# DCI_Connectors.net
KiCad netlist of a schematic drawn in Altium Designer
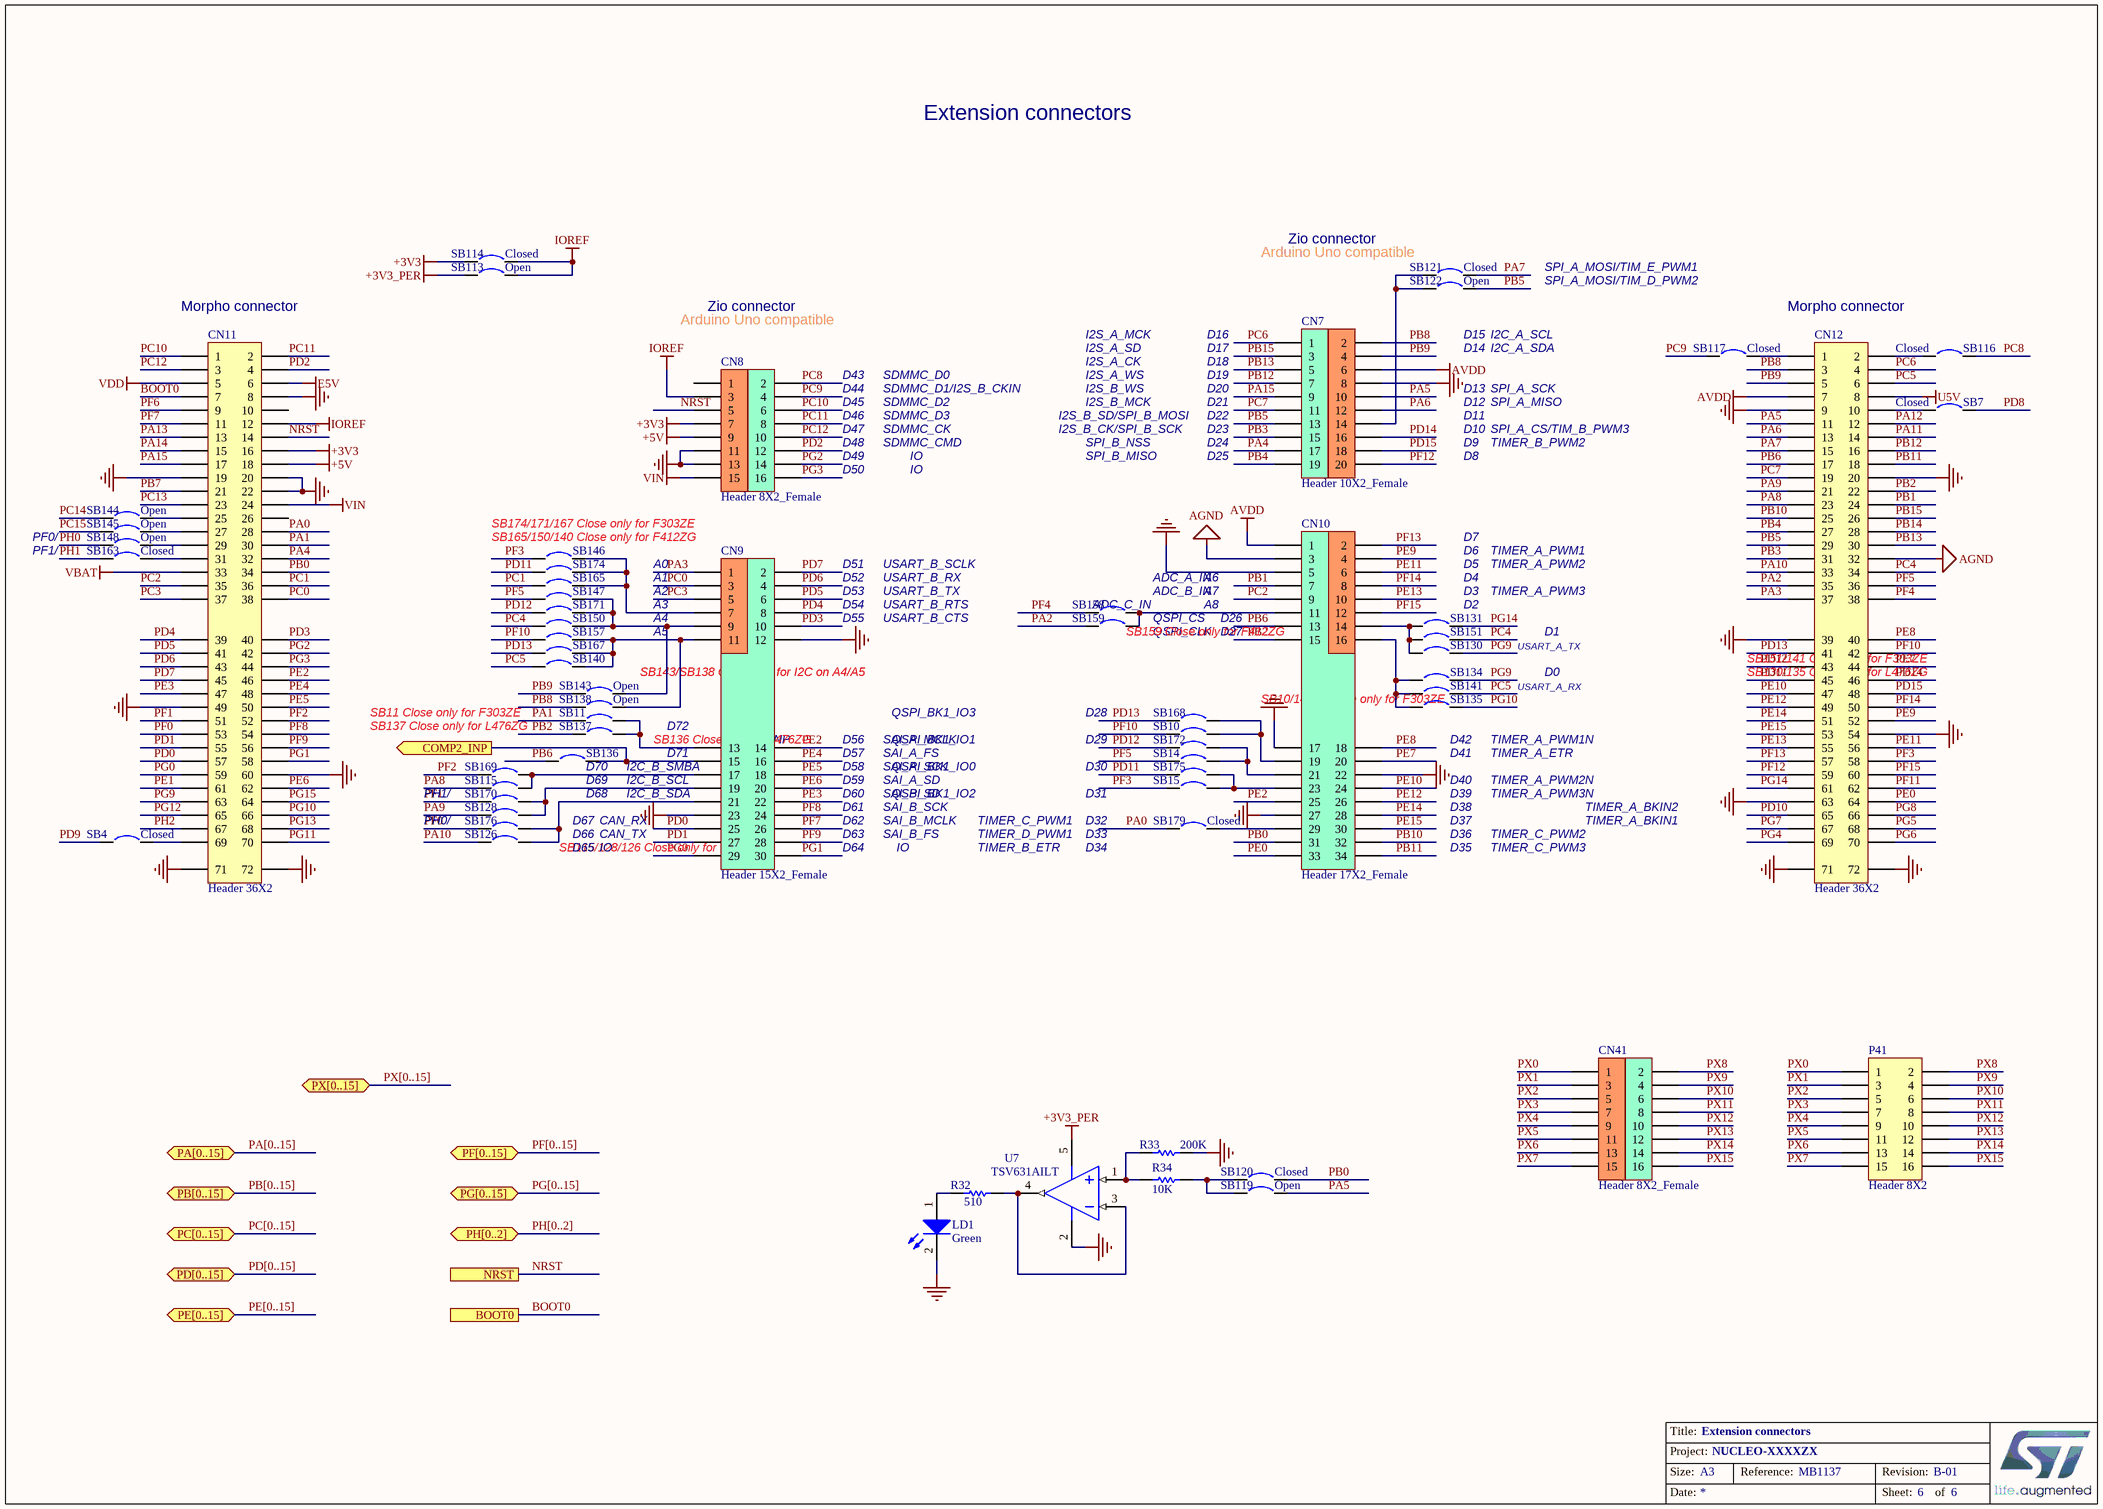
[diagram p0: DCI_Connectors.SchDoc]

(export (version "E")
  (design (tool "Eeschema 10.0.6"))
  (components
    (comp (ref "CN7")
      (value "Header 10X2_Female")
      (footprint "HDR_10x2_2R54_V_F")
      (description "Header, 10-Pin, Dual row,female")
      (fields (field (name "PUBLISHER") "Altium Limited"))
      (libsource (lib "MB1137") (part "Header 10X2_Female"))
    )
    (comp (ref "CN8")
      (value "Header 8X2_Female")
      (footprint "HDR_8x2_2R54_V_F")
      (description "Header, 8-Pin, Dual row,female")
      (fields (field (name "PUBLISHER") "Altium Limited"))
      (libsource (lib "MB1137") (part "Header 8X2_Female"))
    )
    (comp (ref "CN9")
      (value "Header 15X2_Female")
      (footprint "HDR_15x2_2R54_V_F")
      (description "Header, 15-Pin, Dual row,female")
      (fields (field (name "PUBLISHER") "Altium Limited"))
      (libsource (lib "MB1137") (part "Header 15X2_Female"))
    )
    (comp (ref "CN10")
      (value "Header 17X2_Female")
      (footprint "HDR_17x2_2R54_V_F")
      (description "Header, 17-Pin, Dual row,female")
      (fields (field (name "PUBLISHER") "Altium Limited"))
      (libsource (lib "MB1137") (part "Header 17X2_Female"))
    )
    (comp (ref "CN11")
      (value "Header 36X2")
      (footprint "HDR_2x36_2R54_V_M")
      (description "Header, 36-Pin, Dual row")
      (fields (field (name "PUBLISHER") "Altium Limited"))
      (libsource (lib "MB1137") (part "Header 36X2"))
    )
    (comp (ref "CN12")
      (value "Header 36X2")
      (footprint "HDR_2x36_2R54_V_M")
      (description "Header, 36-Pin, Dual row")
      (fields (field (name "PUBLISHER") "Altium Limited"))
      (libsource (lib "MB1137") (part "Header 36X2"))
    )
    (comp (ref "CN41")
      (value "Header 8X2_Female")
      (footprint "HDR_8x2_2R54_V_F")
      (description "Header, 8-Pin, Dual row,female")
      (fields (field (name "PUBLISHER") "Altium Limited"))
      (libsource (lib "MB1137") (part "Header 8X2_Female"))
    )
    (comp (ref "LD1")
      (value "Green")
      (footprint "0603D-G")
      (description "Typical RED, GREEN, YELLOW, AMBER GaAs LED")
      (fields (field (name "PUBLISHER") "Altium Limited"))
      (libsource (lib "Miscellaneous Devices") (part "LED2"))
    )
    (comp (ref "P41")
      (value "Header 8X2")
      (footprint "HDR2X8")
      (description "Header, 8-Pin, Dual row")
      (fields (field (name "PUBLISHER") "Altium Limited"))
      (libsource (lib "Miscellaneous Connectors") (part "Header 8X2"))
    )
    (comp (ref "R32")
      (value "510")
      (footprint "0603R")
      (description "Resistor")
      (fields (field (name "PUBLISHER") "Altium Limited"))
      (libsource (lib "Miscellaneous Devices") (part "Res1"))
    )
    (comp (ref "R33")
      (value "200K")
      (footprint "0603R")
      (description "Resistor")
      (fields (field (name "PUBLISHER") "Altium Limited"))
      (libsource (lib "Miscellaneous Devices") (part "res1"))
    )
    (comp (ref "R34")
      (value "10K")
      (footprint "0603R")
      (description "Resistor")
      (fields (field (name "PUBLISHER") "Altium Limited"))
      (libsource (lib "Miscellaneous Devices") (part "res1"))
    )
    (comp (ref "SB4")
      (value "Closed")
      (footprint "SB_0603")
      (description "Circuit Breaker")
      (fields (field (name "PUBLISHER") "Altium Limited"))
      (libsource (lib "MB1167") (part "Circuit Breaker_close"))
    )
    (comp (ref "SB7")
      (value "Closed")
      (footprint "SB_0603")
      (description "Circuit Breaker")
      (fields (field (name "PUBLISHER") "Altium Limited"))
      (libsource (lib "MB1167") (part "Circuit Breaker_close"))
    )
    (comp (ref "SB10")
      (value "Circuit Breaker")
      (footprint "SB_0603")
      (fields (field (name "PUBLISHER") "Altium Limited"))
      (libsource (lib "") (part "Circuit Breaker_1"))
    )
    (comp (ref "SB11")
      (value "Circuit Breaker")
      (footprint "SB_0603")
      (fields (field (name "PUBLISHER") "Altium Limited"))
      (libsource (lib "MCD_TOOLS") (part "Circuit Breaker"))
    )
    (comp (ref "SB14")
      (value "Circuit Breaker")
      (footprint "SB_0603")
      (fields (field (name "PUBLISHER") "Altium Limited"))
      (libsource (lib "") (part "Circuit Breaker_1"))
    )
    (comp (ref "SB15")
      (value "Circuit Breaker")
      (footprint "SB_0603")
      (fields (field (name "PUBLISHER") "Altium Limited"))
      (libsource (lib "") (part "Circuit Breaker_1"))
    )
    (comp (ref "SB113")
      (value "Open")
      (footprint "SB_0603")
      (description "Circuit Breaker")
      (fields (field (name "PUBLISHER") "Altium Limited"))
      (libsource (lib "MB1167") (part "Circuit Breaker"))
    )
    (comp (ref "SB114")
      (value "Closed")
      (footprint "SB_0603")
      (description "Circuit Breaker")
      (fields (field (name "PUBLISHER") "Altium Limited"))
      (libsource (lib "MB1167") (part "Circuit Breaker_close"))
    )
    (comp (ref "SB115")
      (value "Circuit Breaker")
      (footprint "SB_0603")
      (fields (field (name "PUBLISHER") "Altium Limited"))
      (libsource (lib "MCD_TOOLS") (part "Circuit Breaker"))
    )
    (comp (ref "SB116")
      (value "Closed")
      (footprint "SB_0603")
      (description "Circuit Breaker")
      (fields (field (name "PUBLISHER") "Altium Limited"))
      (libsource (lib "") (part "Circuit Breaker_close_1"))
    )
    (comp (ref "SB117")
      (value "Closed")
      (footprint "SB_0603")
      (description "Circuit Breaker")
      (fields (field (name "PUBLISHER") "Altium Limited"))
      (libsource (lib "MB1167") (part "Circuit Breaker_close"))
    )
    (comp (ref "SB119")
      (value "Open")
      (footprint "SB_0603")
      (description "Circuit Breaker")
      (fields (field (name "PUBLISHER") "Altium Limited"))
      (libsource (lib "MB1167") (part "Circuit Breaker"))
    )
    (comp (ref "SB120")
      (value "Closed")
      (footprint "SB_0603")
      (description "Circuit Breaker")
      (fields (field (name "PUBLISHER") "Altium Limited"))
      (libsource (lib "") (part "Circuit Breaker_close_1"))
    )
    (comp (ref "SB121")
      (value "Closed")
      (footprint "SB_0603")
      (description "Circuit Breaker")
      (fields (field (name "PUBLISHER") "Altium Limited"))
      (libsource (lib "MB1167") (part "Circuit Breaker_close"))
    )
    (comp (ref "SB122")
      (value "Open")
      (footprint "SB_0603")
      (description "Circuit Breaker")
      (fields (field (name "PUBLISHER") "Altium Limited"))
      (libsource (lib "MB1167") (part "Circuit Breaker"))
    )
    (comp (ref "SB126")
      (value "Circuit Breaker")
      (footprint "SB_0603")
      (fields (field (name "PUBLISHER") "Altium Limited"))
      (libsource (lib "MCD_TOOLS") (part "Circuit Breaker"))
    )
    (comp (ref "SB128")
      (value "Circuit Breaker")
      (footprint "SB_0603")
      (fields (field (name "PUBLISHER") "Altium Limited"))
      (libsource (lib "MCD_TOOLS") (part "Circuit Breaker"))
    )
    (comp (ref "SB130")
      (value "Circuit Breaker")
      (footprint "SB_0603")
      (fields (field (name "PUBLISHER") "Altium Limited"))
      (libsource (lib "MCD_TOOLS") (part "Circuit Breaker"))
    )
    (comp (ref "SB131")
      (value "Circuit Breaker")
      (footprint "SB_0603")
      (fields (field (name "PUBLISHER") "Altium Limited"))
      (libsource (lib "MCD_TOOLS") (part "Circuit Breaker"))
    )
    (comp (ref "SB134")
      (value "Circuit Breaker")
      (footprint "SB_0603")
      (fields (field (name "PUBLISHER") "Altium Limited"))
      (libsource (lib "MCD_TOOLS") (part "Circuit Breaker"))
    )
    (comp (ref "SB135")
      (value "Circuit Breaker")
      (footprint "SB_0603")
      (fields (field (name "PUBLISHER") "Altium Limited"))
      (libsource (lib "MCD_TOOLS") (part "Circuit Breaker"))
    )
    (comp (ref "SB136")
      (value "Circuit Breaker")
      (footprint "SB_0603")
      (fields (field (name "PUBLISHER") "Altium Limited"))
      (libsource (lib "MCD_TOOLS") (part "Circuit Breaker"))
    )
    (comp (ref "SB137")
      (value "Circuit Breaker")
      (footprint "SB_0603")
      (fields (field (name "PUBLISHER") "Altium Limited"))
      (libsource (lib "MCD_TOOLS") (part "Circuit Breaker"))
    )
    (comp (ref "SB138")
      (value "Open")
      (footprint "SB_0603")
      (description "Circuit Breaker")
      (fields (field (name "PUBLISHER") "Altium Limited"))
      (libsource (lib "") (part "Circuit Breaker_1"))
    )
    (comp (ref "SB140")
      (value "Circuit Breaker")
      (footprint "SB_0603")
      (fields (field (name "PUBLISHER") "Altium Limited"))
      (libsource (lib "MCD_TOOLS") (part "Circuit Breaker"))
    )
    (comp (ref "SB141")
      (value "Circuit Breaker")
      (footprint "SB_0603")
      (fields (field (name "PUBLISHER") "Altium Limited"))
      (libsource (lib "MCD_TOOLS") (part "Circuit Breaker"))
    )
    (comp (ref "SB143")
      (value "Open")
      (footprint "SB_0603")
      (description "Circuit Breaker")
      (fields (field (name "PUBLISHER") "Altium Limited"))
      (libsource (lib "") (part "Circuit Breaker_1"))
    )
    (comp (ref "SB144")
      (value "Open")
      (footprint "SB_0603")
      (description "Circuit Breaker")
      (fields (field (name "PUBLISHER") "Altium Limited"))
      (libsource (lib "MB1167") (part "Circuit Breaker"))
    )
    (comp (ref "SB145")
      (value "Open")
      (footprint "SB_0603")
      (description "Circuit Breaker")
      (fields (field (name "PUBLISHER") "Altium Limited"))
      (libsource (lib "MB1167") (part "Circuit Breaker"))
    )
    (comp (ref "SB146")
      (value "Circuit Breaker")
      (footprint "SB_0603")
      (fields (field (name "PUBLISHER") "Altium Limited"))
      (libsource (lib "MCD_TOOLS") (part "Circuit Breaker"))
    )
    (comp (ref "SB147")
      (value "Circuit Breaker")
      (footprint "SB_0603")
      (fields (field (name "PUBLISHER") "Altium Limited"))
      (libsource (lib "MCD_TOOLS") (part "Circuit Breaker"))
    )
    (comp (ref "SB148")
      (value "Open")
      (footprint "SB_0603")
      (description "Circuit Breaker")
      (fields (field (name "PUBLISHER") "Altium Limited"))
      (libsource (lib "MB1167") (part "Circuit Breaker"))
    )
    (comp (ref "SB150")
      (value "Circuit Breaker")
      (footprint "SB_0603")
      (fields (field (name "PUBLISHER") "Altium Limited"))
      (libsource (lib "MCD_TOOLS") (part "Circuit Breaker"))
    )
    (comp (ref "SB151")
      (value "Circuit Breaker")
      (footprint "SB_0603")
      (fields (field (name "PUBLISHER") "Altium Limited"))
      (libsource (lib "MCD_TOOLS") (part "Circuit Breaker"))
    )
    (comp (ref "SB157")
      (value "Circuit Breaker")
      (footprint "SB_0603")
      (fields (field (name "PUBLISHER") "Altium Limited"))
      (libsource (lib "MCD_TOOLS") (part "Circuit Breaker"))
    )
    (comp (ref "SB158")
      (value "Circuit Breaker")
      (footprint "SB_0603")
      (fields (field (name "PUBLISHER") "Altium Limited"))
      (libsource (lib "") (part "Circuit Breaker_1"))
    )
    (comp (ref "SB159")
      (value "Circuit Breaker")
      (footprint "SB_0603")
      (fields (field (name "PUBLISHER") "Altium Limited"))
      (libsource (lib "") (part "Circuit Breaker_1"))
    )
    (comp (ref "SB163")
      (value "Closed")
      (footprint "SB_0603")
      (description "Circuit Breaker")
      (fields (field (name "PUBLISHER") "Altium Limited"))
      (libsource (lib "MB1167") (part "Circuit Breaker_close"))
    )
    (comp (ref "SB165")
      (value "Circuit Breaker")
      (footprint "SB_0603")
      (fields (field (name "PUBLISHER") "Altium Limited"))
      (libsource (lib "MCD_TOOLS") (part "Circuit Breaker"))
    )
    (comp (ref "SB167")
      (value "Circuit Breaker")
      (footprint "SB_0603")
      (fields (field (name "PUBLISHER") "Altium Limited"))
      (libsource (lib "MCD_TOOLS") (part "Circuit Breaker"))
    )
    (comp (ref "SB168")
      (value "Circuit Breaker")
      (footprint "SB_0603")
      (fields (field (name "PUBLISHER") "Altium Limited"))
      (libsource (lib "") (part "Circuit Breaker_1"))
    )
    (comp (ref "SB169")
      (value "Circuit Breaker")
      (footprint "SB_0603")
      (fields (field (name "PUBLISHER") "Altium Limited"))
      (libsource (lib "MCD_TOOLS") (part "Circuit Breaker"))
    )
    (comp (ref "SB170")
      (value "Circuit Breaker")
      (footprint "SB_0603")
      (fields (field (name "PUBLISHER") "Altium Limited"))
      (libsource (lib "MCD_TOOLS") (part "Circuit Breaker"))
    )
    (comp (ref "SB171")
      (value "Circuit Breaker")
      (footprint "SB_0603")
      (fields (field (name "PUBLISHER") "Altium Limited"))
      (libsource (lib "MCD_TOOLS") (part "Circuit Breaker"))
    )
    (comp (ref "SB172")
      (value "Circuit Breaker")
      (footprint "SB_0603")
      (fields (field (name "PUBLISHER") "Altium Limited"))
      (libsource (lib "") (part "Circuit Breaker_1"))
    )
    (comp (ref "SB174")
      (value "Circuit Breaker")
      (footprint "SB_0603")
      (fields (field (name "PUBLISHER") "Altium Limited"))
      (libsource (lib "MCD_TOOLS") (part "Circuit Breaker"))
    )
    (comp (ref "SB175")
      (value "Circuit Breaker")
      (footprint "SB_0603")
      (fields (field (name "PUBLISHER") "Altium Limited"))
      (libsource (lib "") (part "Circuit Breaker_1"))
    )
    (comp (ref "SB176")
      (value "Circuit Breaker")
      (footprint "SB_0603")
      (fields (field (name "PUBLISHER") "Altium Limited"))
      (libsource (lib "MCD_TOOLS") (part "Circuit Breaker"))
    )
    (comp (ref "SB179")
      (value "Closed")
      (footprint "SB_0603")
      (description "Circuit Breaker")
      (fields (field (name "PUBLISHER") "Altium Limited"))
      (libsource (lib "MB1167") (part "Circuit Breaker_close"))
    )
    (comp (ref "U7")
      (value "TSV631AILT")
      (footprint "SOT-23-5L")
      (libsource (lib "MB988") (part "TSV631AILT"))
    )
  )
  (nets
    (net (code "1") (name "+3V3") (class "Default")
      (node (ref "CN11") (pin "16") (pinfunction "16_16") (pintype "passive"))
      (node (ref "CN8") (pin "7") (pinfunction "7_7") (pintype "passive"))
      (node (ref "SB114") (pin "1") (pinfunction "1_1") (pintype "passive"))
    )
    (net (code "2") (name "+3V3_PER") (class "Default")
      (node (ref "SB113") (pin "1") (pinfunction "1_1") (pintype "passive"))
      (node (ref "U7") (pin "5") (pinfunction "VCC_5") (pintype "power_in"))
    )
    (net (code "3") (name "+5V") (class "Default")
      (node (ref "CN11") (pin "18") (pinfunction "18_18") (pintype "passive"))
      (node (ref "CN8") (pin "9") (pinfunction "9_9") (pintype "passive"))
    )
    (net (code "4") (name "/BOOT0") (class "Default")
      (node (ref "CN11") (pin "7") (pinfunction "7_7") (pintype "passive"))
    )
    (net (code "5") (name "/COMP2_INP") (class "Default")
      (node (ref "CN9") (pin "15") (pinfunction "15_15") (pintype "passive"))
      (node (ref "SB136") (pin "1") (pinfunction "1_1") (pintype "passive"))
    )
    (net (code "6") (name "/NRST") (class "Default")
      (node (ref "CN11") (pin "14") (pinfunction "14_14") (pintype "passive"))
      (node (ref "CN8") (pin "5") (pinfunction "5_5") (pintype "passive"))
    )
    (net (code "7") (name "/PA0") (class "Default")
      (node (ref "CN11") (pin "28") (pinfunction "28_28") (pintype "passive"))
      (node (ref "SB179") (pin "1") (pinfunction "1_1") (pintype "passive"))
    )
    (net (code "8") (name "/PA1") (class "Default")
      (node (ref "CN11") (pin "30") (pinfunction "30_30") (pintype "passive"))
      (node (ref "SB11") (pin "2") (pinfunction "2_2") (pintype "passive"))
    )
    (net (code "9") (name "/PA2") (class "Default")
      (node (ref "CN12") (pin "35") (pinfunction "35_35") (pintype "passive"))
      (node (ref "SB159") (pin "1") (pinfunction "1_1") (pintype "passive"))
    )
    (net (code "10") (name "/PA3") (class "Default")
      (node (ref "CN12") (pin "37") (pinfunction "37_37") (pintype "passive"))
      (node (ref "CN9") (pin "1") (pinfunction "1_1") (pintype "passive"))
    )
    (net (code "11") (name "/PA4") (class "Default")
      (node (ref "CN11") (pin "32") (pinfunction "32_32") (pintype "passive"))
      (node (ref "CN7") (pin "17") (pinfunction "17_17") (pintype "passive"))
    )
    (net (code "12") (name "/PA5") (class "Default")
      (node (ref "CN12") (pin "11") (pinfunction "11_11") (pintype "passive"))
      (node (ref "CN7") (pin "10") (pinfunction "10_10") (pintype "passive"))
      (node (ref "SB119") (pin "2") (pinfunction "2_2") (pintype "passive"))
    )
    (net (code "13") (name "/PA6") (class "Default")
      (node (ref "CN12") (pin "13") (pinfunction "13_13") (pintype "passive"))
      (node (ref "CN7") (pin "12") (pinfunction "12_12") (pintype "passive"))
    )
    (net (code "14") (name "/PA7") (class "Default")
      (node (ref "CN12") (pin "15") (pinfunction "15_15") (pintype "passive"))
      (node (ref "SB121") (pin "2") (pinfunction "2_2") (pintype "passive"))
    )
    (net (code "15") (name "/PA8") (class "Default")
      (node (ref "CN12") (pin "23") (pinfunction "23_23") (pintype "passive"))
      (node (ref "SB115") (pin "2") (pinfunction "2_2") (pintype "passive"))
    )
    (net (code "16") (name "/PA9") (class "Default")
      (node (ref "CN12") (pin "21") (pinfunction "21_21") (pintype "passive"))
      (node (ref "SB128") (pin "2") (pinfunction "2_2") (pintype "passive"))
    )
    (net (code "17") (name "/PA10") (class "Default")
      (node (ref "CN12") (pin "33") (pinfunction "33_33") (pintype "passive"))
      (node (ref "SB126") (pin "2") (pinfunction "2_2") (pintype "passive"))
    )
    (net (code "18") (name "/PA11") (class "Default")
      (node (ref "CN12") (pin "14") (pinfunction "14_14") (pintype "passive"))
    )
    (net (code "19") (name "/PA12") (class "Default")
      (node (ref "CN12") (pin "12") (pinfunction "12_12") (pintype "passive"))
    )
    (net (code "20") (name "/PA13") (class "Default")
      (node (ref "CN11") (pin "13") (pinfunction "13_13") (pintype "passive"))
    )
    (net (code "21") (name "/PA14") (class "Default")
      (node (ref "CN11") (pin "15") (pinfunction "15_15") (pintype "passive"))
    )
    (net (code "22") (name "/PA15") (class "Default")
      (node (ref "CN11") (pin "17") (pinfunction "17_17") (pintype "passive"))
      (node (ref "CN7") (pin "9") (pinfunction "9_9") (pintype "passive"))
    )
    (net (code "24") (name "/PB0") (class "Default")
      (node (ref "CN10") (pin "31") (pinfunction "31_31") (pintype "passive"))
      (node (ref "CN11") (pin "34") (pinfunction "34_34") (pintype "passive"))
      (node (ref "SB120") (pin "1") (pinfunction "1_1") (pintype "passive"))
    )
    (net (code "25") (name "/PB1") (class "Default")
      (node (ref "CN10") (pin "7") (pinfunction "7_7") (pintype "passive"))
      (node (ref "CN12") (pin "24") (pinfunction "24_24") (pintype "passive"))
    )
    (net (code "26") (name "/PB2") (class "Default")
      (node (ref "CN10") (pin "15") (pinfunction "15_15") (pintype "passive"))
      (node (ref "CN12") (pin "22") (pinfunction "22_22") (pintype "passive"))
      (node (ref "SB137") (pin "2") (pinfunction "2_2") (pintype "passive"))
    )
    (net (code "27") (name "/PB3") (class "Default")
      (node (ref "CN12") (pin "31") (pinfunction "31_31") (pintype "passive"))
      (node (ref "CN7") (pin "15") (pinfunction "15_15") (pintype "passive"))
    )
    (net (code "28") (name "/PB4") (class "Default")
      (node (ref "CN12") (pin "27") (pinfunction "27_27") (pintype "passive"))
      (node (ref "CN7") (pin "19") (pinfunction "19_19") (pintype "passive"))
    )
    (net (code "29") (name "/PB5") (class "Default")
      (node (ref "CN12") (pin "29") (pinfunction "29_29") (pintype "passive"))
      (node (ref "CN7") (pin "13") (pinfunction "13_13") (pintype "passive"))
      (node (ref "SB122") (pin "2") (pinfunction "2_2") (pintype "passive"))
    )
    (net (code "30") (name "/PB6") (class "Default")
      (node (ref "CN10") (pin "13") (pinfunction "13_13") (pintype "passive"))
      (node (ref "CN12") (pin "17") (pinfunction "17_17") (pintype "passive"))
      (node (ref "SB136") (pin "2") (pinfunction "2_2") (pintype "passive"))
    )
    (net (code "31") (name "/PB7") (class "Default")
      (node (ref "CN11") (pin "21") (pinfunction "21_21") (pintype "passive"))
    )
    (net (code "32") (name "/PB8") (class "Default")
      (node (ref "CN12") (pin "3") (pinfunction "3_3") (pintype "passive"))
      (node (ref "CN7") (pin "2") (pinfunction "2_2") (pintype "passive"))
      (node (ref "SB138") (pin "2") (pinfunction "2_2") (pintype "passive"))
    )
    (net (code "33") (name "/PB9") (class "Default")
      (node (ref "CN12") (pin "5") (pinfunction "5_5") (pintype "passive"))
      (node (ref "CN7") (pin "4") (pinfunction "4_4") (pintype "passive"))
      (node (ref "SB143") (pin "2") (pinfunction "2_2") (pintype "passive"))
    )
    (net (code "34") (name "/PB10") (class "Default")
      (node (ref "CN10") (pin "32") (pinfunction "32_32") (pintype "passive"))
      (node (ref "CN12") (pin "25") (pinfunction "25_25") (pintype "passive"))
    )
    (net (code "35") (name "/PB11") (class "Default")
      (node (ref "CN10") (pin "34") (pinfunction "34_34") (pintype "passive"))
      (node (ref "CN12") (pin "18") (pinfunction "18_18") (pintype "passive"))
    )
    (net (code "36") (name "/PB12") (class "Default")
      (node (ref "CN12") (pin "16") (pinfunction "16_16") (pintype "passive"))
      (node (ref "CN7") (pin "7") (pinfunction "7_7") (pintype "passive"))
    )
    (net (code "37") (name "/PB13") (class "Default")
      (node (ref "CN12") (pin "30") (pinfunction "30_30") (pintype "passive"))
      (node (ref "CN7") (pin "5") (pinfunction "5_5") (pintype "passive"))
    )
    (net (code "38") (name "/PB14") (class "Default")
      (node (ref "CN12") (pin "28") (pinfunction "28_28") (pintype "passive"))
    )
    (net (code "39") (name "/PB15") (class "Default")
      (node (ref "CN12") (pin "26") (pinfunction "26_26") (pintype "passive"))
      (node (ref "CN7") (pin "3") (pinfunction "3_3") (pintype "passive"))
    )
    (net (code "41") (name "/PC0") (class "Default")
      (node (ref "CN11") (pin "38") (pinfunction "38_38") (pintype "passive"))
      (node (ref "CN9") (pin "3") (pinfunction "3_3") (pintype "passive"))
    )
    (net (code "42") (name "/PC1") (class "Default")
      (node (ref "CN11") (pin "36") (pinfunction "36_36") (pintype "passive"))
      (node (ref "SB165") (pin "2") (pinfunction "2_2") (pintype "passive"))
    )
    (net (code "43") (name "/PC2") (class "Default")
      (node (ref "CN10") (pin "9") (pinfunction "9_9") (pintype "passive"))
      (node (ref "CN11") (pin "35") (pinfunction "35_35") (pintype "passive"))
    )
    (net (code "44") (name "/PC3") (class "Default")
      (node (ref "CN11") (pin "37") (pinfunction "37_37") (pintype "passive"))
      (node (ref "CN9") (pin "5") (pinfunction "5_5") (pintype "passive"))
    )
    (net (code "45") (name "/PC4") (class "Default")
      (node (ref "CN12") (pin "34") (pinfunction "34_34") (pintype "passive"))
      (node (ref "SB150") (pin "2") (pinfunction "2_2") (pintype "passive"))
      (node (ref "SB151") (pin "1") (pinfunction "1_1") (pintype "passive"))
    )
    (net (code "46") (name "/PC5") (class "Default")
      (node (ref "CN12") (pin "6") (pinfunction "6_6") (pintype "passive"))
      (node (ref "SB140") (pin "2") (pinfunction "2_2") (pintype "passive"))
      (node (ref "SB141") (pin "1") (pinfunction "1_1") (pintype "passive"))
    )
    (net (code "47") (name "/PC6") (class "Default")
      (node (ref "CN12") (pin "4") (pinfunction "4_4") (pintype "passive"))
      (node (ref "CN7") (pin "1") (pinfunction "1_1") (pintype "passive"))
    )
    (net (code "48") (name "/PC7") (class "Default")
      (node (ref "CN12") (pin "19") (pinfunction "19_19") (pintype "passive"))
      (node (ref "CN7") (pin "11") (pinfunction "11_11") (pintype "passive"))
    )
    (net (code "49") (name "/PC8") (class "Default")
      (node (ref "CN8") (pin "2") (pinfunction "2_2") (pintype "passive"))
      (node (ref "SB116") (pin "1") (pinfunction "1_1") (pintype "passive"))
    )
    (net (code "50") (name "/PC9") (class "Default")
      (node (ref "CN8") (pin "4") (pinfunction "4_4") (pintype "passive"))
      (node (ref "SB117") (pin "1") (pinfunction "1_1") (pintype "passive"))
    )
    (net (code "51") (name "/PC10") (class "Default")
      (node (ref "CN11") (pin "1") (pinfunction "1_1") (pintype "passive"))
      (node (ref "CN8") (pin "6") (pinfunction "6_6") (pintype "passive"))
    )
    (net (code "52") (name "/PC11") (class "Default")
      (node (ref "CN11") (pin "2") (pinfunction "2_2") (pintype "passive"))
      (node (ref "CN8") (pin "8") (pinfunction "8_8") (pintype "passive"))
    )
    (net (code "53") (name "/PC12") (class "Default")
      (node (ref "CN11") (pin "3") (pinfunction "3_3") (pintype "passive"))
      (node (ref "CN8") (pin "10") (pinfunction "10_10") (pintype "passive"))
    )
    (net (code "54") (name "/PC13") (class "Default")
      (node (ref "CN11") (pin "23") (pinfunction "23_23") (pintype "passive"))
    )
    (net (code "55") (name "/PC14") (class "Default")
      (node (ref "SB144") (pin "1") (pinfunction "1_1") (pintype "passive"))
    )
    (net (code "56") (name "/PC15") (class "Default")
      (node (ref "SB145") (pin "1") (pinfunction "1_1") (pintype "passive"))
    )
    (net (code "58") (name "/PD0") (class "Default")
      (node (ref "CN11") (pin "57") (pinfunction "57_57") (pintype "passive"))
      (node (ref "CN9") (pin "25") (pinfunction "25_25") (pintype "passive"))
    )
    (net (code "59") (name "/PD1") (class "Default")
      (node (ref "CN11") (pin "55") (pinfunction "55_55") (pintype "passive"))
      (node (ref "CN9") (pin "27") (pinfunction "27_27") (pintype "passive"))
    )
    (net (code "60") (name "/PD2") (class "Default")
      (node (ref "CN11") (pin "4") (pinfunction "4_4") (pintype "passive"))
      (node (ref "CN8") (pin "12") (pinfunction "12_12") (pintype "passive"))
    )
    (net (code "61") (name "/PD3") (class "Default")
      (node (ref "CN11") (pin "40") (pinfunction "40_40") (pintype "passive"))
      (node (ref "CN9") (pin "10") (pinfunction "10_10") (pintype "passive"))
    )
    (net (code "62") (name "/PD4") (class "Default")
      (node (ref "CN11") (pin "39") (pinfunction "39_39") (pintype "passive"))
      (node (ref "CN9") (pin "8") (pinfunction "8_8") (pintype "passive"))
    )
    (net (code "63") (name "/PD5") (class "Default")
      (node (ref "CN11") (pin "41") (pinfunction "41_41") (pintype "passive"))
      (node (ref "CN9") (pin "6") (pinfunction "6_6") (pintype "passive"))
    )
    (net (code "64") (name "/PD6") (class "Default")
      (node (ref "CN11") (pin "43") (pinfunction "43_43") (pintype "passive"))
      (node (ref "CN9") (pin "4") (pinfunction "4_4") (pintype "passive"))
    )
    (net (code "65") (name "/PD7") (class "Default")
      (node (ref "CN11") (pin "45") (pinfunction "45_45") (pintype "passive"))
      (node (ref "CN9") (pin "2") (pinfunction "2_2") (pintype "passive"))
    )
    (net (code "66") (name "/PD8") (class "Default")
      (node (ref "SB7") (pin "2") (pinfunction "2_2") (pintype "passive"))
    )
    (net (code "67") (name "/PD9") (class "Default")
      (node (ref "SB4") (pin "1") (pinfunction "1_1") (pintype "passive"))
    )
    (net (code "68") (name "/PD10") (class "Default")
      (node (ref "CN12") (pin "65") (pinfunction "65_65") (pintype "passive"))
    )
    (net (code "69") (name "/PD11") (class "Default")
      (node (ref "CN12") (pin "45") (pinfunction "45_45") (pintype "passive"))
      (node (ref "SB174") (pin "2") (pinfunction "2_2") (pintype "passive"))
      (node (ref "SB175") (pin "1") (pinfunction "1_1") (pintype "passive"))
    )
    (net (code "70") (name "/PD12") (class "Default")
      (node (ref "CN12") (pin "43") (pinfunction "43_43") (pintype "passive"))
      (node (ref "SB171") (pin "2") (pinfunction "2_2") (pintype "passive"))
      (node (ref "SB172") (pin "1") (pinfunction "1_1") (pintype "passive"))
    )
    (net (code "71") (name "/PD13") (class "Default")
      (node (ref "CN12") (pin "41") (pinfunction "41_41") (pintype "passive"))
      (node (ref "SB167") (pin "2") (pinfunction "2_2") (pintype "passive"))
      (node (ref "SB168") (pin "1") (pinfunction "1_1") (pintype "passive"))
    )
    (net (code "72") (name "/PD14") (class "Default")
      (node (ref "CN12") (pin "46") (pinfunction "46_46") (pintype "passive"))
      (node (ref "CN7") (pin "16") (pinfunction "16_16") (pintype "passive"))
    )
    (net (code "73") (name "/PD15") (class "Default")
      (node (ref "CN12") (pin "48") (pinfunction "48_48") (pintype "passive"))
      (node (ref "CN7") (pin "18") (pinfunction "18_18") (pintype "passive"))
    )
    (net (code "75") (name "/PE0") (class "Default")
      (node (ref "CN10") (pin "33") (pinfunction "33_33") (pintype "passive"))
      (node (ref "CN12") (pin "64") (pinfunction "64_64") (pintype "passive"))
    )
    (net (code "76") (name "/PE1") (class "Default")
      (node (ref "CN11") (pin "61") (pinfunction "61_61") (pintype "passive"))
    )
    (net (code "77") (name "/PE2") (class "Default")
      (node (ref "CN10") (pin "25") (pinfunction "25_25") (pintype "passive"))
      (node (ref "CN11") (pin "46") (pinfunction "46_46") (pintype "passive"))
      (node (ref "CN9") (pin "14") (pinfunction "14_14") (pintype "passive"))
    )
    (net (code "78") (name "/PE3") (class "Default")
      (node (ref "CN11") (pin "47") (pinfunction "47_47") (pintype "passive"))
      (node (ref "CN9") (pin "22") (pinfunction "22_22") (pintype "passive"))
    )
    (net (code "79") (name "/PE4") (class "Default")
      (node (ref "CN11") (pin "48") (pinfunction "48_48") (pintype "passive"))
      (node (ref "CN9") (pin "16") (pinfunction "16_16") (pintype "passive"))
    )
    (net (code "80") (name "/PE5") (class "Default")
      (node (ref "CN11") (pin "50") (pinfunction "50_50") (pintype "passive"))
      (node (ref "CN9") (pin "18") (pinfunction "18_18") (pintype "passive"))
    )
    (net (code "81") (name "/PE6") (class "Default")
      (node (ref "CN11") (pin "62") (pinfunction "62_62") (pintype "passive"))
      (node (ref "CN9") (pin "20") (pinfunction "20_20") (pintype "passive"))
    )
    (net (code "82") (name "/PE7") (class "Default")
      (node (ref "CN10") (pin "20") (pinfunction "20_20") (pintype "passive"))
      (node (ref "CN12") (pin "44") (pinfunction "44_44") (pintype "passive"))
    )
    (net (code "83") (name "/PE8") (class "Default")
      (node (ref "CN10") (pin "18") (pinfunction "18_18") (pintype "passive"))
      (node (ref "CN12") (pin "40") (pinfunction "40_40") (pintype "passive"))
    )
    (net (code "84") (name "/PE9") (class "Default")
      (node (ref "CN10") (pin "4") (pinfunction "4_4") (pintype "passive"))
      (node (ref "CN12") (pin "52") (pinfunction "52_52") (pintype "passive"))
    )
    (net (code "85") (name "/PE10") (class "Default")
      (node (ref "CN10") (pin "24") (pinfunction "24_24") (pintype "passive"))
      (node (ref "CN12") (pin "47") (pinfunction "47_47") (pintype "passive"))
    )
    (net (code "86") (name "/PE11") (class "Default")
      (node (ref "CN10") (pin "6") (pinfunction "6_6") (pintype "passive"))
      (node (ref "CN12") (pin "56") (pinfunction "56_56") (pintype "passive"))
    )
    (net (code "87") (name "/PE12") (class "Default")
      (node (ref "CN10") (pin "26") (pinfunction "26_26") (pintype "passive"))
      (node (ref "CN12") (pin "49") (pinfunction "49_49") (pintype "passive"))
    )
    (net (code "88") (name "/PE13") (class "Default")
      (node (ref "CN10") (pin "10") (pinfunction "10_10") (pintype "passive"))
      (node (ref "CN12") (pin "55") (pinfunction "55_55") (pintype "passive"))
    )
    (net (code "89") (name "/PE14") (class "Default")
      (node (ref "CN10") (pin "28") (pinfunction "28_28") (pintype "passive"))
      (node (ref "CN12") (pin "51") (pinfunction "51_51") (pintype "passive"))
    )
    (net (code "90") (name "/PE15") (class "Default")
      (node (ref "CN10") (pin "30") (pinfunction "30_30") (pintype "passive"))
      (node (ref "CN12") (pin "53") (pinfunction "53_53") (pintype "passive"))
    )
    (net (code "92") (name "/PF0") (class "Default")
      (node (ref "CN11") (pin "53") (pinfunction "53_53") (pintype "passive"))
      (node (ref "SB176") (pin "2") (pinfunction "2_2") (pintype "passive"))
    )
    (net (code "93") (name "/PF1") (class "Default")
      (node (ref "CN11") (pin "51") (pinfunction "51_51") (pintype "passive"))
      (node (ref "SB170") (pin "2") (pinfunction "2_2") (pintype "passive"))
    )
    (net (code "94") (name "/PF2") (class "Default")
      (node (ref "CN11") (pin "52") (pinfunction "52_52") (pintype "passive"))
      (node (ref "SB169") (pin "2") (pinfunction "2_2") (pintype "passive"))
    )
    (net (code "95") (name "/PF3") (class "Default")
      (node (ref "CN12") (pin "58") (pinfunction "58_58") (pintype "passive"))
      (node (ref "SB146") (pin "2") (pinfunction "2_2") (pintype "passive"))
      (node (ref "SB15") (pin "1") (pinfunction "1_1") (pintype "passive"))
    )
    (net (code "96") (name "/PF4") (class "Default")
      (node (ref "CN12") (pin "38") (pinfunction "38_38") (pintype "passive"))
      (node (ref "SB158") (pin "1") (pinfunction "1_1") (pintype "passive"))
    )
    (net (code "97") (name "/PF5") (class "Default")
      (node (ref "CN12") (pin "36") (pinfunction "36_36") (pintype "passive"))
      (node (ref "SB14") (pin "1") (pinfunction "1_1") (pintype "passive"))
      (node (ref "SB147") (pin "2") (pinfunction "2_2") (pintype "passive"))
    )
    (net (code "98") (name "/PF6") (class "Default")
      (node (ref "CN11") (pin "9") (pinfunction "9_9") (pintype "passive"))
    )
    (net (code "99") (name "/PF7") (class "Default")
      (node (ref "CN11") (pin "11") (pinfunction "11_11") (pintype "passive"))
      (node (ref "CN9") (pin "26") (pinfunction "26_26") (pintype "passive"))
    )
    (net (code "100") (name "/PF8") (class "Default")
      (node (ref "CN11") (pin "54") (pinfunction "54_54") (pintype "passive"))
      (node (ref "CN9") (pin "24") (pinfunction "24_24") (pintype "passive"))
    )
    (net (code "101") (name "/PF9") (class "Default")
      (node (ref "CN11") (pin "56") (pinfunction "56_56") (pintype "passive"))
      (node (ref "CN9") (pin "28") (pinfunction "28_28") (pintype "passive"))
    )
    (net (code "102") (name "/PF10") (class "Default")
      (node (ref "CN12") (pin "42") (pinfunction "42_42") (pintype "passive"))
      (node (ref "SB10") (pin "1") (pinfunction "1_1") (pintype "passive"))
      (node (ref "SB157") (pin "2") (pinfunction "2_2") (pintype "passive"))
    )
    (net (code "103") (name "/PF11") (class "Default")
      (node (ref "CN12") (pin "62") (pinfunction "62_62") (pintype "passive"))
    )
    (net (code "104") (name "/PF12") (class "Default")
      (node (ref "CN12") (pin "59") (pinfunction "59_59") (pintype "passive"))
      (node (ref "CN7") (pin "20") (pinfunction "20_20") (pintype "passive"))
    )
    (net (code "105") (name "/PF13") (class "Default")
      (node (ref "CN10") (pin "2") (pinfunction "2_2") (pintype "passive"))
      (node (ref "CN12") (pin "57") (pinfunction "57_57") (pintype "passive"))
    )
    (net (code "106") (name "/PF14") (class "Default")
      (node (ref "CN10") (pin "8") (pinfunction "8_8") (pintype "passive"))
      (node (ref "CN12") (pin "50") (pinfunction "50_50") (pintype "passive"))
    )
    (net (code "107") (name "/PF15") (class "Default")
      (node (ref "CN10") (pin "12") (pinfunction "12_12") (pintype "passive"))
      (node (ref "CN12") (pin "60") (pinfunction "60_60") (pintype "passive"))
    )
    (net (code "109") (name "/PG0") (class "Default")
      (node (ref "CN11") (pin "59") (pinfunction "59_59") (pintype "passive"))
      (node (ref "CN9") (pin "29") (pinfunction "29_29") (pintype "passive"))
    )
    (net (code "110") (name "/PG1") (class "Default")
      (node (ref "CN11") (pin "58") (pinfunction "58_58") (pintype "passive"))
      (node (ref "CN9") (pin "30") (pinfunction "30_30") (pintype "passive"))
    )
    (net (code "111") (name "/PG2") (class "Default")
      (node (ref "CN11") (pin "42") (pinfunction "42_42") (pintype "passive"))
      (node (ref "CN8") (pin "14") (pinfunction "14_14") (pintype "passive"))
    )
    (net (code "112") (name "/PG3") (class "Default")
      (node (ref "CN11") (pin "44") (pinfunction "44_44") (pintype "passive"))
      (node (ref "CN8") (pin "16") (pinfunction "16_16") (pintype "passive"))
    )
    (net (code "113") (name "/PG4") (class "Default")
      (node (ref "CN12") (pin "69") (pinfunction "69_69") (pintype "passive"))
    )
    (net (code "114") (name "/PG5") (class "Default")
      (node (ref "CN12") (pin "68") (pinfunction "68_68") (pintype "passive"))
    )
    (net (code "115") (name "/PG6") (class "Default")
      (node (ref "CN12") (pin "70") (pinfunction "70_70") (pintype "passive"))
    )
    (net (code "116") (name "/PG7") (class "Default")
      (node (ref "CN12") (pin "67") (pinfunction "67_67") (pintype "passive"))
    )
    (net (code "117") (name "/PG8") (class "Default")
      (node (ref "CN12") (pin "66") (pinfunction "66_66") (pintype "passive"))
    )
    (net (code "118") (name "/PG9") (class "Default")
      (node (ref "CN11") (pin "63") (pinfunction "63_63") (pintype "passive"))
      (node (ref "SB130") (pin "1") (pinfunction "1_1") (pintype "passive"))
      (node (ref "SB134") (pin "1") (pinfunction "1_1") (pintype "passive"))
    )
    (net (code "119") (name "/PG10") (class "Default")
      (node (ref "CN11") (pin "66") (pinfunction "66_66") (pintype "passive"))
      (node (ref "SB135") (pin "1") (pinfunction "1_1") (pintype "passive"))
    )
    (net (code "120") (name "/PG11") (class "Default")
      (node (ref "CN11") (pin "70") (pinfunction "70_70") (pintype "passive"))
    )
    (net (code "121") (name "/PG12") (class "Default")
      (node (ref "CN11") (pin "65") (pinfunction "65_65") (pintype "passive"))
    )
    (net (code "122") (name "/PG13") (class "Default")
      (node (ref "CN11") (pin "68") (pinfunction "68_68") (pintype "passive"))
    )
    (net (code "123") (name "/PG14") (class "Default")
      (node (ref "CN12") (pin "61") (pinfunction "61_61") (pintype "passive"))
      (node (ref "SB131") (pin "1") (pinfunction "1_1") (pintype "passive"))
    )
    (net (code "124") (name "/PG15") (class "Default")
      (node (ref "CN11") (pin "64") (pinfunction "64_64") (pintype "passive"))
    )
    (net (code "126") (name "/PH0") (class "Default")
      (node (ref "SB148") (pin "1") (pinfunction "1_1") (pintype "passive"))
    )
    (net (code "127") (name "/PH1") (class "Default")
      (node (ref "SB163") (pin "1") (pinfunction "1_1") (pintype "passive"))
    )
    (net (code "128") (name "/PH2") (class "Default")
      (node (ref "CN11") (pin "67") (pinfunction "67_67") (pintype "passive"))
    )
    (net (code "130") (name "/PX0") (class "Default")
      (node (ref "CN41") (pin "1") (pinfunction "1_1") (pintype "passive"))
      (node (ref "P41") (pin "1") (pinfunction "1_1") (pintype "passive"))
    )
    (net (code "131") (name "/PX1") (class "Default")
      (node (ref "CN41") (pin "3") (pinfunction "3_3") (pintype "passive"))
      (node (ref "P41") (pin "3") (pinfunction "3_3") (pintype "passive"))
    )
    (net (code "132") (name "/PX2") (class "Default")
      (node (ref "CN41") (pin "5") (pinfunction "5_5") (pintype "passive"))
      (node (ref "P41") (pin "5") (pinfunction "5_5") (pintype "passive"))
    )
    (net (code "133") (name "/PX3") (class "Default")
      (node (ref "CN41") (pin "7") (pinfunction "7_7") (pintype "passive"))
      (node (ref "P41") (pin "7") (pinfunction "7_7") (pintype "passive"))
    )
    (net (code "134") (name "/PX4") (class "Default")
      (node (ref "CN41") (pin "9") (pinfunction "9_9") (pintype "passive"))
      (node (ref "P41") (pin "9") (pinfunction "9_9") (pintype "passive"))
    )
    (net (code "135") (name "/PX5") (class "Default")
      (node (ref "CN41") (pin "11") (pinfunction "11_11") (pintype "passive"))
      (node (ref "P41") (pin "11") (pinfunction "11_11") (pintype "passive"))
    )
    (net (code "136") (name "/PX6") (class "Default")
      (node (ref "CN41") (pin "13") (pinfunction "13_13") (pintype "passive"))
      (node (ref "P41") (pin "13") (pinfunction "13_13") (pintype "passive"))
    )
    (net (code "137") (name "/PX7") (class "Default")
      (node (ref "CN41") (pin "15") (pinfunction "15_15") (pintype "passive"))
      (node (ref "P41") (pin "15") (pinfunction "15_15") (pintype "passive"))
    )
    (net (code "138") (name "/PX8") (class "Default")
      (node (ref "CN41") (pin "2") (pinfunction "2_2") (pintype "passive"))
      (node (ref "P41") (pin "2") (pinfunction "2_2") (pintype "passive"))
    )
    (net (code "139") (name "/PX9") (class "Default")
      (node (ref "CN41") (pin "4") (pinfunction "4_4") (pintype "passive"))
      (node (ref "P41") (pin "4") (pinfunction "4_4") (pintype "passive"))
    )
    (net (code "140") (name "/PX10") (class "Default")
      (node (ref "CN41") (pin "6") (pinfunction "6_6") (pintype "passive"))
      (node (ref "P41") (pin "6") (pinfunction "6_6") (pintype "passive"))
    )
    (net (code "141") (name "/PX11") (class "Default")
      (node (ref "CN41") (pin "8") (pinfunction "8_8") (pintype "passive"))
      (node (ref "P41") (pin "8") (pinfunction "8_8") (pintype "passive"))
    )
    (net (code "142") (name "/PX12") (class "Default")
      (node (ref "CN41") (pin "10") (pinfunction "10_10") (pintype "passive"))
      (node (ref "P41") (pin "10") (pinfunction "10_10") (pintype "passive"))
    )
    (net (code "143") (name "/PX13") (class "Default")
      (node (ref "CN41") (pin "12") (pinfunction "12_12") (pintype "passive"))
      (node (ref "P41") (pin "12") (pinfunction "12_12") (pintype "passive"))
    )
    (net (code "144") (name "/PX14") (class "Default")
      (node (ref "CN41") (pin "14") (pinfunction "14_14") (pintype "passive"))
      (node (ref "P41") (pin "14") (pinfunction "14_14") (pintype "passive"))
    )
    (net (code "145") (name "/PX15") (class "Default")
      (node (ref "CN41") (pin "16") (pinfunction "16_16") (pintype "passive"))
      (node (ref "P41") (pin "16") (pinfunction "16_16") (pintype "passive"))
    )
    (net (code "147") (name "AGND") (class "Default")
      (node (ref "CN10") (pin "3") (pinfunction "3_3") (pintype "passive"))
      (node (ref "CN12") (pin "32") (pinfunction "32_32") (pintype "passive"))
    )
    (net (code "148") (name "AVDD") (class "Default")
      (node (ref "CN10") (pin "1") (pinfunction "1_1") (pintype "passive"))
      (node (ref "CN12") (pin "7") (pinfunction "7_7") (pintype "passive"))
      (node (ref "CN7") (pin "6") (pinfunction "6_6") (pintype "passive"))
    )
    (net (code "149") (name "E5V") (class "Default")
      (node (ref "CN11") (pin "6") (pinfunction "6_6") (pintype "passive"))
    )
    (net (code "150") (name "GND") (class "Default")
      (node (ref "CN10") (pin "17") (pinfunction "17_17") (pintype "passive"))
      (node (ref "CN10") (pin "22") (pinfunction "22_22") (pintype "passive"))
      (node (ref "CN10") (pin "27") (pinfunction "27_27") (pintype "passive"))
      (node (ref "CN10") (pin "5") (pinfunction "5_5") (pintype "passive"))
      (node (ref "CN11") (pin "19") (pinfunction "19_19") (pintype "passive"))
      (node (ref "CN11") (pin "20") (pinfunction "20_20") (pintype "passive"))
      (node (ref "CN11") (pin "22") (pinfunction "22_22") (pintype "passive"))
      (node (ref "CN11") (pin "49") (pinfunction "49_49") (pintype "passive"))
      (node (ref "CN11") (pin "60") (pinfunction "60_60") (pintype "passive"))
      (node (ref "CN11") (pin "71") (pinfunction "71_71") (pintype "passive"))
      (node (ref "CN11") (pin "72") (pinfunction "72_72") (pintype "passive"))
      (node (ref "CN11") (pin "8") (pinfunction "8_8") (pintype "passive"))
      (node (ref "CN12") (pin "20") (pinfunction "20_20") (pintype "passive"))
      (node (ref "CN12") (pin "39") (pinfunction "39_39") (pintype "passive"))
      (node (ref "CN12") (pin "54") (pinfunction "54_54") (pintype "passive"))
      (node (ref "CN12") (pin "63") (pinfunction "63_63") (pintype "passive"))
      (node (ref "CN12") (pin "71") (pinfunction "71_71") (pintype "passive"))
      (node (ref "CN12") (pin "72") (pinfunction "72_72") (pintype "passive"))
      (node (ref "CN12") (pin "9") (pinfunction "9_9") (pintype "passive"))
      (node (ref "CN7") (pin "8") (pinfunction "8_8") (pintype "passive"))
      (node (ref "CN8") (pin "11") (pinfunction "11_11") (pintype "passive"))
      (node (ref "CN8") (pin "13") (pinfunction "13_13") (pintype "passive"))
      (node (ref "CN9") (pin "12") (pinfunction "12_12") (pintype "passive"))
      (node (ref "CN9") (pin "23") (pinfunction "23_23") (pintype "passive"))
      (node (ref "LD1") (pin "2") (pinfunction "K_2") (pintype "passive"))
      (node (ref "R33") (pin "2") (pinfunction "2_2") (pintype "passive"))
      (node (ref "U7") (pin "2") (pinfunction "VDD_2") (pintype "power_in"))
    )
    (net (code "151") (name "IOREF") (class "Default")
      (node (ref "CN11") (pin "12") (pinfunction "12_12") (pintype "passive"))
      (node (ref "CN8") (pin "3") (pinfunction "3_3") (pintype "passive"))
      (node (ref "SB113") (pin "2") (pinfunction "2_2") (pintype "passive"))
      (node (ref "SB114") (pin "2") (pinfunction "2_2") (pintype "passive"))
    )
    (net (code "152") (name "Net-(CN7-Pad14)") (class "Default")
      (node (ref "CN7") (pin "14") (pinfunction "14_14") (pintype "passive"))
      (node (ref "SB121") (pin "1") (pinfunction "1_1") (pintype "passive"))
      (node (ref "SB122") (pin "1") (pinfunction "1_1") (pintype "passive"))
    )
    (net (code "153") (name "Net-(CN9-Pad7)") (class "Default")
      (node (ref "CN9") (pin "7") (pinfunction "7_7") (pintype "passive"))
      (node (ref "SB146") (pin "1") (pinfunction "1_1") (pintype "passive"))
      (node (ref "SB165") (pin "1") (pinfunction "1_1") (pintype "passive"))
      (node (ref "SB174") (pin "1") (pinfunction "1_1") (pintype "passive"))
    )
    (net (code "154") (name "Net-(CN9-Pad9)") (class "Default")
      (node (ref "CN9") (pin "9") (pinfunction "9_9") (pintype "passive"))
      (node (ref "SB143") (pin "1") (pinfunction "1_1") (pintype "passive"))
      (node (ref "SB147") (pin "1") (pinfunction "1_1") (pintype "passive"))
      (node (ref "SB150") (pin "1") (pinfunction "1_1") (pintype "passive"))
      (node (ref "SB171") (pin "1") (pinfunction "1_1") (pintype "passive"))
    )
    (net (code "155") (name "Net-(CN9-Pad11)") (class "Default")
      (node (ref "CN9") (pin "11") (pinfunction "11_11") (pintype "passive"))
      (node (ref "SB138") (pin "1") (pinfunction "1_1") (pintype "passive"))
      (node (ref "SB140") (pin "1") (pinfunction "1_1") (pintype "passive"))
      (node (ref "SB157") (pin "1") (pinfunction "1_1") (pintype "passive"))
      (node (ref "SB167") (pin "1") (pinfunction "1_1") (pintype "passive"))
    )
    (net (code "156") (name "Net-(CN9-Pad13)") (class "Default")
      (node (ref "CN9") (pin "13") (pinfunction "13_13") (pintype "passive"))
      (node (ref "SB11") (pin "1") (pinfunction "1_1") (pintype "passive"))
      (node (ref "SB137") (pin "1") (pinfunction "1_1") (pintype "passive"))
    )
    (net (code "157") (name "Net-(CN9-Pad17)") (class "Default")
      (node (ref "CN9") (pin "17") (pinfunction "17_17") (pintype "passive"))
      (node (ref "SB115") (pin "1") (pinfunction "1_1") (pintype "passive"))
      (node (ref "SB169") (pin "1") (pinfunction "1_1") (pintype "passive"))
    )
    (net (code "158") (name "Net-(CN9-Pad19)") (class "Default")
      (node (ref "CN9") (pin "19") (pinfunction "19_19") (pintype "passive"))
      (node (ref "SB128") (pin "1") (pinfunction "1_1") (pintype "passive"))
      (node (ref "SB170") (pin "1") (pinfunction "1_1") (pintype "passive"))
    )
    (net (code "159") (name "Net-(CN9-Pad21)") (class "Default")
      (node (ref "CN9") (pin "21") (pinfunction "21_21") (pintype "passive"))
      (node (ref "SB126") (pin "1") (pinfunction "1_1") (pintype "passive"))
      (node (ref "SB176") (pin "1") (pinfunction "1_1") (pintype "passive"))
    )
    (net (code "160") (name "Net-(CN10-Pad11)") (class "Default")
      (node (ref "CN10") (pin "11") (pinfunction "11_11") (pintype "passive"))
      (node (ref "SB158") (pin "2") (pinfunction "2_2") (pintype "passive"))
      (node (ref "SB159") (pin "2") (pinfunction "2_2") (pintype "passive"))
    )
    (net (code "161") (name "Net-(CN10-Pad14)") (class "Default")
      (node (ref "CN10") (pin "14") (pinfunction "14_14") (pintype "passive"))
      (node (ref "SB130") (pin "2") (pinfunction "2_2") (pintype "passive"))
      (node (ref "SB131") (pin "2") (pinfunction "2_2") (pintype "passive"))
      (node (ref "SB151") (pin "2") (pinfunction "2_2") (pintype "passive"))
    )
    (net (code "162") (name "Net-(CN10-Pad16)") (class "Default")
      (node (ref "CN10") (pin "16") (pinfunction "16_16") (pintype "passive"))
      (node (ref "SB134") (pin "2") (pinfunction "2_2") (pintype "passive"))
      (node (ref "SB135") (pin "2") (pinfunction "2_2") (pintype "passive"))
      (node (ref "SB141") (pin "2") (pinfunction "2_2") (pintype "passive"))
    )
    (net (code "163") (name "Net-(CN10-Pad19)") (class "Default")
      (node (ref "CN10") (pin "19") (pinfunction "19_19") (pintype "passive"))
      (node (ref "SB10") (pin "2") (pinfunction "2_2") (pintype "passive"))
      (node (ref "SB168") (pin "2") (pinfunction "2_2") (pintype "passive"))
    )
    (net (code "164") (name "Net-(CN10-Pad21)") (class "Default")
      (node (ref "CN10") (pin "21") (pinfunction "21_21") (pintype "passive"))
      (node (ref "SB14") (pin "2") (pinfunction "2_2") (pintype "passive"))
      (node (ref "SB172") (pin "2") (pinfunction "2_2") (pintype "passive"))
    )
    (net (code "165") (name "Net-(CN10-Pad23)") (class "Default")
      (node (ref "CN10") (pin "23") (pinfunction "23_23") (pintype "passive"))
      (node (ref "SB15") (pin "2") (pinfunction "2_2") (pintype "passive"))
      (node (ref "SB175") (pin "2") (pinfunction "2_2") (pintype "passive"))
    )
    (net (code "166") (name "Net-(CN10-Pad29)") (class "Default")
      (node (ref "CN10") (pin "29") (pinfunction "29_29") (pintype "passive"))
      (node (ref "SB179") (pin "2") (pinfunction "2_2") (pintype "passive"))
    )
    (net (code "167") (name "Net-(CN11-Pad25)") (class "Default")
      (node (ref "CN11") (pin "25") (pinfunction "25_25") (pintype "passive"))
      (node (ref "SB144") (pin "2") (pinfunction "2_2") (pintype "passive"))
    )
    (net (code "168") (name "Net-(CN11-Pad27)") (class "Default")
      (node (ref "CN11") (pin "27") (pinfunction "27_27") (pintype "passive"))
      (node (ref "SB145") (pin "2") (pinfunction "2_2") (pintype "passive"))
    )
    (net (code "169") (name "Net-(CN11-Pad29)") (class "Default")
      (node (ref "CN11") (pin "29") (pinfunction "29_29") (pintype "passive"))
      (node (ref "SB148") (pin "2") (pinfunction "2_2") (pintype "passive"))
    )
    (net (code "170") (name "Net-(CN11-Pad31)") (class "Default")
      (node (ref "CN11") (pin "31") (pinfunction "31_31") (pintype "passive"))
      (node (ref "SB163") (pin "2") (pinfunction "2_2") (pintype "passive"))
    )
    (net (code "171") (name "Net-(CN11-Pad69)") (class "Default")
      (node (ref "CN11") (pin "69") (pinfunction "69_69") (pintype "passive"))
      (node (ref "SB4") (pin "2") (pinfunction "2_2") (pintype "passive"))
    )
    (net (code "172") (name "Net-(CN12-Pad1)") (class "Default")
      (node (ref "CN12") (pin "1") (pinfunction "1_1") (pintype "passive"))
      (node (ref "SB117") (pin "2") (pinfunction "2_2") (pintype "passive"))
    )
    (net (code "173") (name "Net-(CN12-Pad2)") (class "Default")
      (node (ref "CN12") (pin "2") (pinfunction "2_2") (pintype "passive"))
      (node (ref "SB116") (pin "2") (pinfunction "2_2") (pintype "passive"))
    )
    (net (code "174") (name "Net-(CN12-Pad10)") (class "Default")
      (node (ref "CN12") (pin "10") (pinfunction "10_10") (pintype "passive"))
      (node (ref "SB7") (pin "1") (pinfunction "1_1") (pintype "passive"))
    )
    (net (code "175") (name "Net-(LD1-A)") (class "Default")
      (node (ref "LD1") (pin "1") (pinfunction "A_1") (pintype "passive"))
      (node (ref "R32") (pin "2") (pinfunction "2_2") (pintype "passive"))
    )
    (net (code "176") (name "Net-(R34-Pad2)") (class "Default")
      (node (ref "R34") (pin "2") (pinfunction "2_2") (pintype "passive"))
      (node (ref "SB119") (pin "1") (pinfunction "1_1") (pintype "passive"))
      (node (ref "SB120") (pin "2") (pinfunction "2_2") (pintype "passive"))
    )
    (net (code "177") (name "Net-(U7-IN+)") (class "Default")
      (node (ref "R33") (pin "1") (pinfunction "1_1") (pintype "passive"))
      (node (ref "R34") (pin "1") (pinfunction "1_1") (pintype "passive"))
      (node (ref "U7") (pin "1") (pinfunction "IN+_1") (pintype "input"))
    )
    (net (code "178") (name "Net-(U7-IN-)") (class "Default")
      (node (ref "R32") (pin "1") (pinfunction "1_1") (pintype "passive"))
      (node (ref "U7") (pin "3") (pinfunction "IN-_3") (pintype "input"))
      (node (ref "U7") (pin "4") (pinfunction "OUT_4") (pintype "output"))
    )
    (net (code "179") (name "U5V") (class "Default")
      (node (ref "CN12") (pin "8") (pinfunction "8_8") (pintype "passive"))
    )
    (net (code "180") (name "VBAT") (class "Default")
      (node (ref "CN11") (pin "33") (pinfunction "33_33") (pintype "passive"))
    )
    (net (code "181") (name "VDD") (class "Default")
      (node (ref "CN11") (pin "5") (pinfunction "5_5") (pintype "passive"))
    )
    (net (code "182") (name "VIN") (class "Default")
      (node (ref "CN11") (pin "24") (pinfunction "24_24") (pintype "passive"))
      (node (ref "CN8") (pin "15") (pinfunction "15_15") (pintype "passive"))
    )
    (net (code "183") (name "unconnected-(CN8-Pad1)") (class "Default")
      (node (ref "CN8") (pin "1") (pinfunction "1_1") (pintype "passive"))
    )
    (net (code "184") (name "unconnected-(CN11-Pad10)") (class "Default")
      (node (ref "CN11") (pin "10") (pinfunction "10_10") (pintype "passive"))
    )
    (net (code "185") (name "unconnected-(CN11-Pad26)") (class "Default")
      (node (ref "CN11") (pin "26") (pinfunction "26_26") (pintype "passive"))
    )
  )
)
